# ngptv.net
KiCad netlist of a schematic drawn in EAGLE
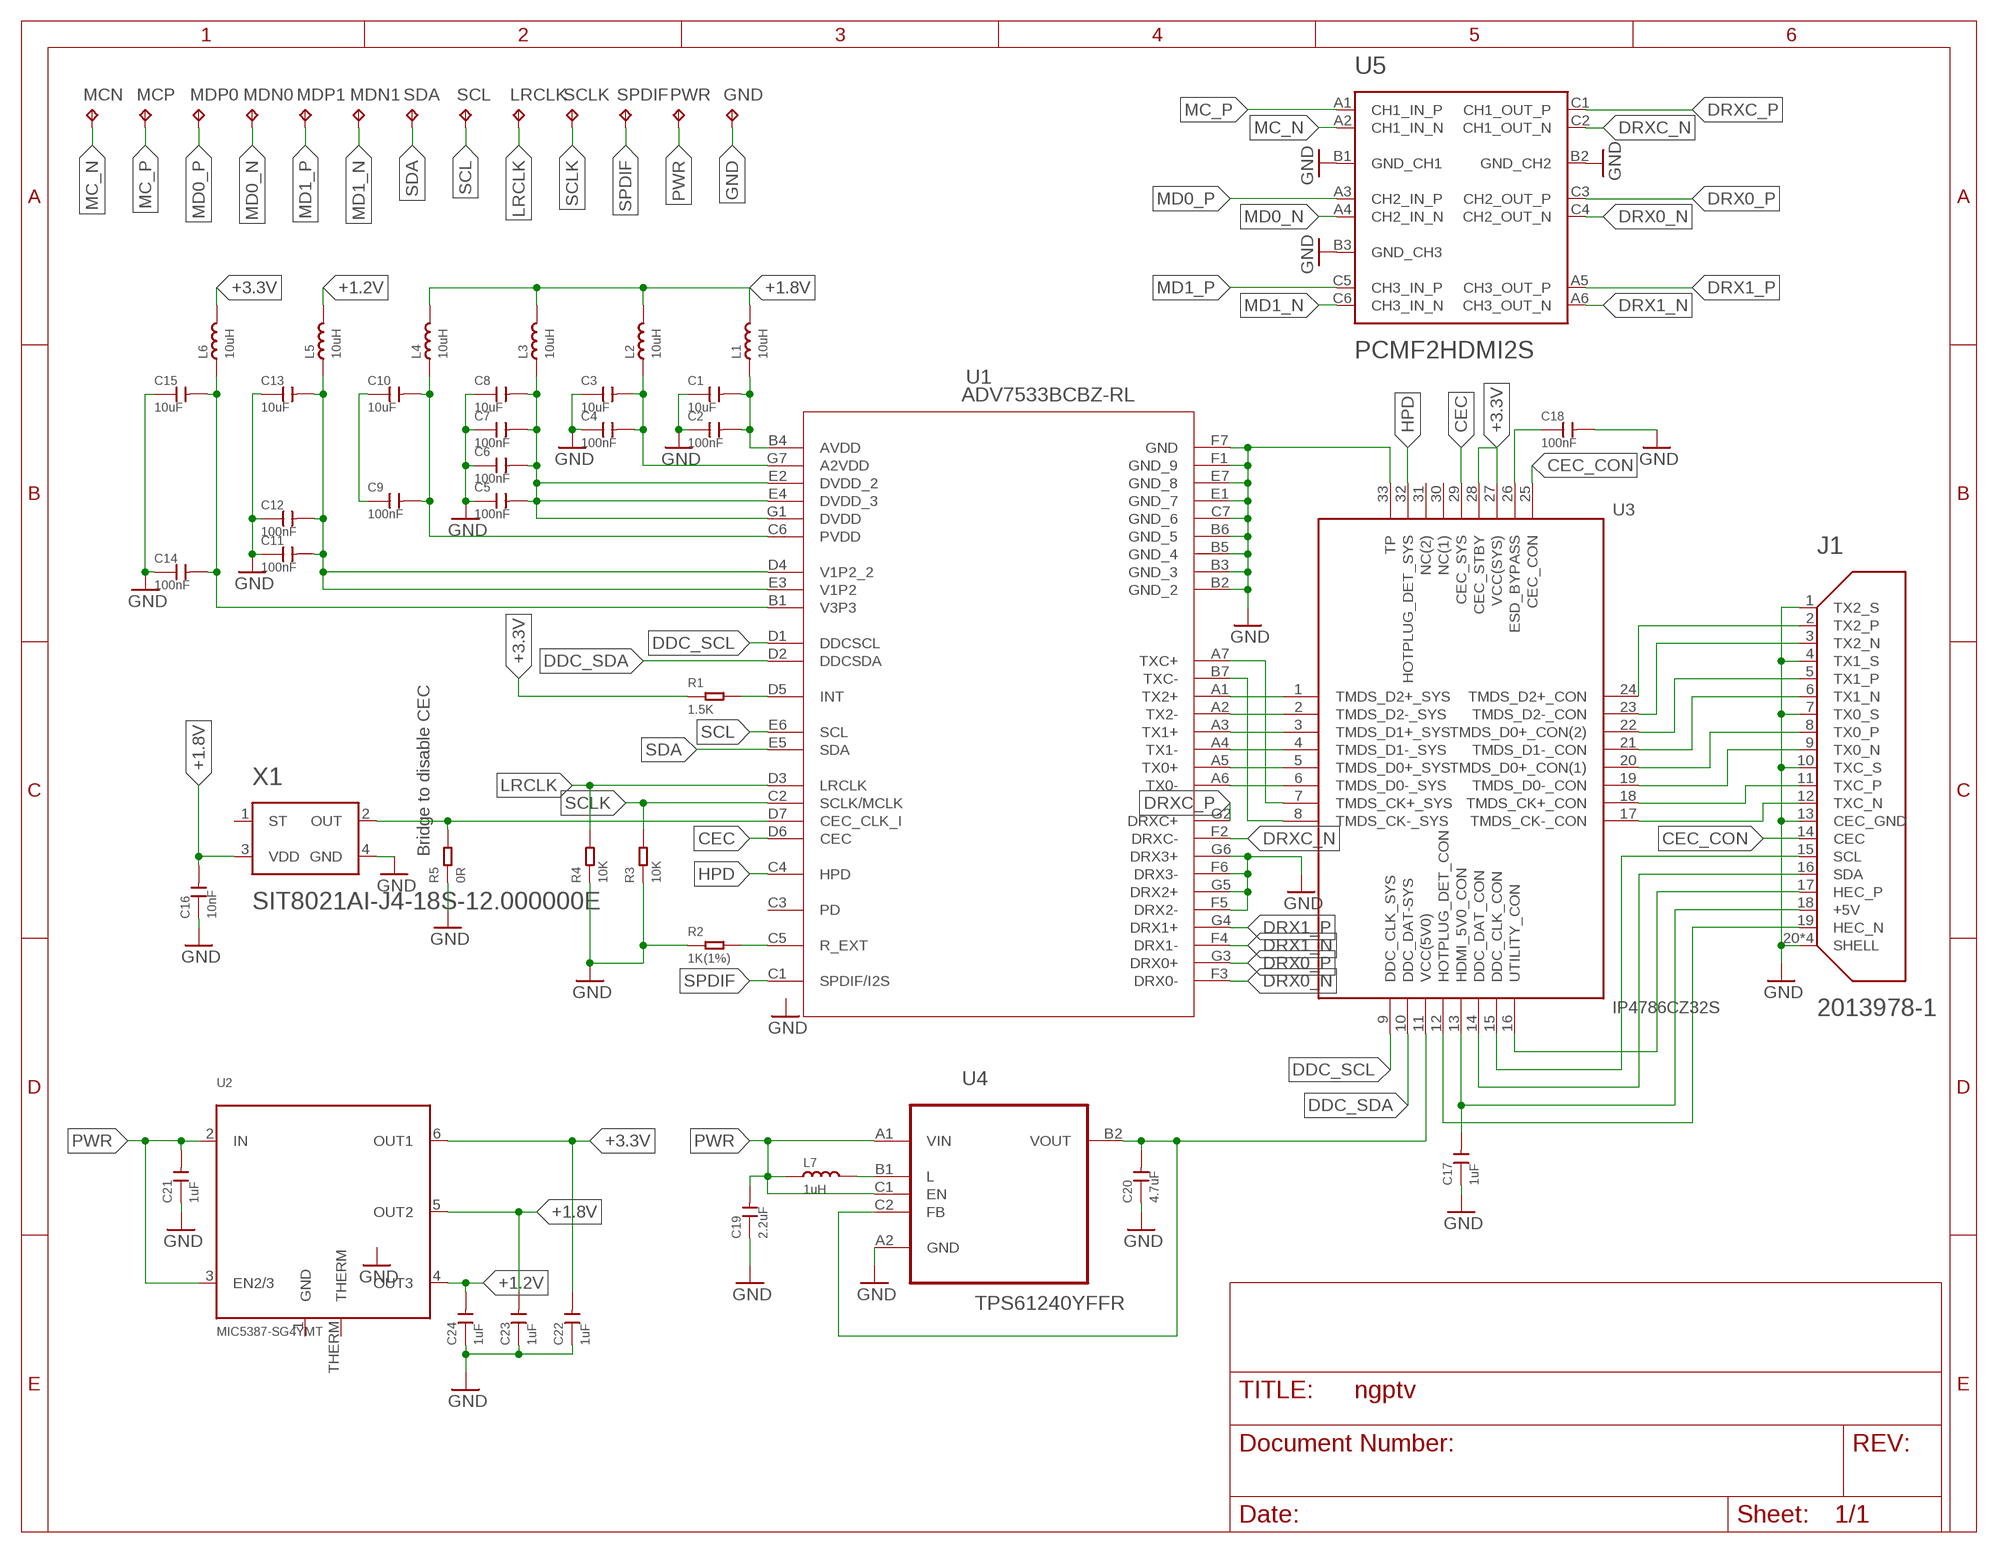
[diagram p0: schematic, sheet 1]

(export (version "E")
  (design (tool "Eeschema 10.0.6"))
  (components
    (comp (ref "C1")
      (value "10uF")
      (footprint "eagle-import:C0402")
      (fields (field (name "MPN") "CC0402MRX5R5BB106"))
      (libsource (lib "eagle-import") (part "CERAMIC-10UF-6.3V-20%-X5R(0402)"))
    )
    (comp (ref "C2")
      (value "100nF")
      (footprint "eagle-import:C0402")
      (fields (field (name "MPN") "CC0402MRX5R5BB106"))
      (libsource (lib "eagle-import") (part "CERAMIC-10UF-6.3V-20%-X5R(0402)"))
    )
    (comp (ref "C3")
      (value "10uF")
      (footprint "eagle-import:C0402")
      (fields (field (name "MPN") "CC0402MRX5R5BB106"))
      (libsource (lib "eagle-import") (part "CERAMIC-10UF-6.3V-20%-X5R(0402)"))
    )
    (comp (ref "C4")
      (value "100nF")
      (footprint "eagle-import:C0402")
      (fields (field (name "MPN") "CC0402MRX5R5BB106"))
      (libsource (lib "eagle-import") (part "CERAMIC-10UF-6.3V-20%-X5R(0402)"))
    )
    (comp (ref "C5")
      (value "100nF")
      (footprint "eagle-import:C0402")
      (fields (field (name "MPN") "CC0402MRX5R5BB106"))
      (libsource (lib "eagle-import") (part "CERAMIC-10UF-6.3V-20%-X5R(0402)"))
    )
    (comp (ref "C6")
      (value "100nF")
      (footprint "eagle-import:C0402")
      (fields (field (name "MPN") "CC0402MRX5R5BB106"))
      (libsource (lib "eagle-import") (part "CERAMIC-10UF-6.3V-20%-X5R(0402)"))
    )
    (comp (ref "C7")
      (value "100nF")
      (footprint "eagle-import:C0402")
      (fields (field (name "MPN") "CC0402MRX5R5BB106"))
      (libsource (lib "eagle-import") (part "CERAMIC-10UF-6.3V-20%-X5R(0402)"))
    )
    (comp (ref "C8")
      (value "10uF")
      (footprint "eagle-import:C0402")
      (fields (field (name "MPN") "CC0402MRX5R5BB106"))
      (libsource (lib "eagle-import") (part "CERAMIC-10UF-6.3V-20%-X5R(0402)"))
    )
    (comp (ref "C9")
      (value "100nF")
      (footprint "eagle-import:C0402")
      (fields (field (name "MPN") "CC0402MRX5R5BB106"))
      (libsource (lib "eagle-import") (part "CERAMIC-10UF-6.3V-20%-X5R(0402)"))
    )
    (comp (ref "C10")
      (value "10uF")
      (footprint "eagle-import:C0402")
      (fields (field (name "MPN") "CC0402MRX5R5BB106"))
      (libsource (lib "eagle-import") (part "CERAMIC-10UF-6.3V-20%-X5R(0402)"))
    )
    (comp (ref "C11")
      (value "100nF")
      (footprint "eagle-import:C0402")
      (fields (field (name "MPN") "CC0402MRX5R5BB106"))
      (libsource (lib "eagle-import") (part "CERAMIC-10UF-6.3V-20%-X5R(0402)"))
    )
    (comp (ref "C12")
      (value "100nF")
      (footprint "eagle-import:C0402")
      (fields (field (name "MPN") "CC0402MRX5R5BB106"))
      (libsource (lib "eagle-import") (part "CERAMIC-10UF-6.3V-20%-X5R(0402)"))
    )
    (comp (ref "C13")
      (value "10uF")
      (footprint "eagle-import:C0402")
      (fields (field (name "MPN") "CC0402MRX5R5BB106"))
      (libsource (lib "eagle-import") (part "CERAMIC-10UF-6.3V-20%-X5R(0402)"))
    )
    (comp (ref "C14")
      (value "100nF")
      (footprint "eagle-import:C0402")
      (fields (field (name "MPN") "CC0402MRX5R5BB106"))
      (libsource (lib "eagle-import") (part "CERAMIC-10UF-6.3V-20%-X5R(0402)"))
    )
    (comp (ref "C15")
      (value "10uF")
      (footprint "eagle-import:C0402")
      (fields (field (name "MPN") "CC0402MRX5R5BB106"))
      (libsource (lib "eagle-import") (part "CERAMIC-10UF-6.3V-20%-X5R(0402)"))
    )
    (comp (ref "C16")
      (value "10nF")
      (footprint "eagle-import:C0402")
      (fields (field (name "MPN") "CC0402MRX5R5BB106"))
      (libsource (lib "eagle-import") (part "CERAMIC-10UF-6.3V-20%-X5R(0402)"))
    )
    (comp (ref "C17")
      (value "1uF")
      (footprint "eagle-import:C0402")
      (fields (field (name "MPN") "CC0402KRX5R5BB105"))
      (libsource (lib "eagle-import") (part "CERAMIC-1UF-6.3V-10%-X5R(0402)"))
    )
    (comp (ref "C18")
      (value "100nF")
      (footprint "eagle-import:C0402")
      (fields (field (name "MPN") "CC0402KRX5R5BB105"))
      (libsource (lib "eagle-import") (part "CERAMIC-1UF-6.3V-10%-X5R(0402)"))
    )
    (comp (ref "C19")
      (value "2.2uF")
      (footprint "eagle-import:C0402")
      (fields (field (name "MPN") "CC0402KRX7R9BB222"))
      (libsource (lib "eagle-import") (part "CERAMIC-2.2NF-50V-10%-X7R(0402)"))
    )
    (comp (ref "C20")
      (value "4.7uF")
      (footprint "eagle-import:C0402")
      (fields (field (name "MPN") "CC0402MRX5R5BB475"))
      (libsource (lib "eagle-import") (part "CERAMIC-4.7UF-6.3V-20%-X5R(0402)"))
    )
    (comp (ref "C21")
      (value "1uF")
      (footprint "eagle-import:C0402")
      (fields (field (name "MPN") "CC0402KRX5R5BB105"))
      (libsource (lib "eagle-import") (part "CERAMIC-1UF-6.3V-10%-X5R(0402)"))
    )
    (comp (ref "C22")
      (value "1uF")
      (footprint "eagle-import:C0402")
      (fields (field (name "MPN") "CC0402KRX5R5BB105"))
      (libsource (lib "eagle-import") (part "CERAMIC-1UF-6.3V-10%-X5R(0402)"))
    )
    (comp (ref "C23")
      (value "1uF")
      (footprint "eagle-import:C0402")
      (fields (field (name "MPN") "CC0402KRX5R5BB105"))
      (libsource (lib "eagle-import") (part "CERAMIC-1UF-6.3V-10%-X5R(0402)"))
    )
    (comp (ref "C24")
      (value "1uF")
      (footprint "eagle-import:C0402")
      (fields (field (name "MPN") "CC0402KRX5R5BB105"))
      (libsource (lib "eagle-import") (part "CERAMIC-1UF-6.3V-10%-X5R(0402)"))
    )
    (comp (ref "GND")
      (value "TPTP12R")
      (footprint "eagle-import:TP12R")
      (libsource (lib "eagle-import") (part "TPTP12R"))
    )
    (comp (ref "J1")
      (value "2013978-1")
      (footprint "eagle-import:DIP-SMT")
      (libsource (lib "eagle-import") (part "2013978-1"))
    )
    (comp (ref "L1")
      (value "10uH")
      (footprint "eagle-import:L0603")
      (fields (field (name "MPN") "BLM18AG121SN1D"))
      (libsource (lib "eagle-import") (part "SMD-FERRITE-CHIP-120-OHM-500MA(0603)"))
    )
    (comp (ref "L2")
      (value "10uH")
      (footprint "eagle-import:L0603")
      (fields (field (name "MPN") "BLM18AG121SN1D"))
      (libsource (lib "eagle-import") (part "SMD-FERRITE-CHIP-120-OHM-500MA(0603)"))
    )
    (comp (ref "L3")
      (value "10uH")
      (footprint "eagle-import:L0603")
      (fields (field (name "MPN") "BLM18AG121SN1D"))
      (libsource (lib "eagle-import") (part "SMD-FERRITE-CHIP-120-OHM-500MA(0603)"))
    )
    (comp (ref "L4")
      (value "10uH")
      (footprint "eagle-import:L0603")
      (fields (field (name "MPN") "BLM18AG121SN1D"))
      (libsource (lib "eagle-import") (part "SMD-FERRITE-CHIP-120-OHM-500MA(0603)"))
    )
    (comp (ref "L5")
      (value "10uH")
      (footprint "eagle-import:L0603")
      (fields (field (name "MPN") "BLM18AG121SN1D"))
      (libsource (lib "eagle-import") (part "SMD-FERRITE-CHIP-120-OHM-500MA(0603)"))
    )
    (comp (ref "L6")
      (value "10uH")
      (footprint "eagle-import:L0603")
      (fields (field (name "MPN") "BLM18AG121SN1D"))
      (libsource (lib "eagle-import") (part "SMD-FERRITE-CHIP-120-OHM-500MA(0603)"))
    )
    (comp (ref "L7")
      (value "1uH")
      (footprint "eagle-import:L0603")
      (fields (field (name "MPN") "BLM18AG121SN1D"))
      (libsource (lib "eagle-import") (part "SMD-FERRITE-CHIP-120-OHM-500MA(0603)"))
    )
    (comp (ref "LRCLK")
      (value "TPTP10R")
      (footprint "eagle-import:TP10R")
      (libsource (lib "eagle-import") (part "TPTP10R"))
    )
    (comp (ref "MCN")
      (value "TPTP10R")
      (footprint "eagle-import:TP10R")
      (libsource (lib "eagle-import") (part "TPTP10R"))
    )
    (comp (ref "MCP")
      (value "TPTP10R")
      (footprint "eagle-import:TP10R")
      (libsource (lib "eagle-import") (part "TPTP10R"))
    )
    (comp (ref "MDN0")
      (value "TPTP10R")
      (footprint "eagle-import:TP10R")
      (libsource (lib "eagle-import") (part "TPTP10R"))
    )
    (comp (ref "MDN1")
      (value "TPTP10R")
      (footprint "eagle-import:TP10R")
      (libsource (lib "eagle-import") (part "TPTP10R"))
    )
    (comp (ref "MDP0")
      (value "TPTP10R")
      (footprint "eagle-import:TP10R")
      (libsource (lib "eagle-import") (part "TPTP10R"))
    )
    (comp (ref "MDP1")
      (value "TPTP10R")
      (footprint "eagle-import:TP10R")
      (libsource (lib "eagle-import") (part "TPTP10R"))
    )
    (comp (ref "PWR")
      (value "TPTP12R")
      (footprint "eagle-import:TP12R")
      (libsource (lib "eagle-import") (part "TPTP12R"))
    )
    (comp (ref "R1")
      (value "1.5K")
      (footprint "eagle-import:R0402")
      (fields (field (name "MPN") "RC0402JR-071K5L"))
      (libsource (lib "eagle-import") (part "SMD-RES-1.5K-5%-1/16W(0402)"))
    )
    (comp (ref "R2")
      (value "1K(1%)")
      (footprint "eagle-import:R0402")
      (fields (field (name "MPN") "RC0402JR-071K5L"))
      (libsource (lib "eagle-import") (part "SMD-RES-1.5K-5%-1/16W(0402)"))
    )
    (comp (ref "R3")
      (value "10K")
      (footprint "eagle-import:R0402")
      (fields (field (name "MPN") "RC0402FR-0710KL"))
      (libsource (lib "eagle-import") (part "SMD-RES-10K-1%-1/16W(0402)"))
    )
    (comp (ref "R4")
      (value "10K")
      (footprint "eagle-import:R0402")
      (fields (field (name "MPN") "RC0402FR-0710KL"))
      (libsource (lib "eagle-import") (part "SMD-RES-10K-1%-1/16W(0402)"))
    )
    (comp (ref "R5")
      (value "0R")
      (footprint "eagle-import:R0402")
      (fields (field (name "MPN") "RC0402JR-070RL"))
      (libsource (lib "eagle-import") (part "SMD-RES-0R-5%-1/16W(0402)"))
    )
    (comp (ref "SCL")
      (value "TPTP10R")
      (footprint "eagle-import:TP10R")
      (libsource (lib "eagle-import") (part "TPTP10R"))
    )
    (comp (ref "SCLK")
      (value "TPTP10R")
      (footprint "eagle-import:TP10R")
      (libsource (lib "eagle-import") (part "TPTP10R"))
    )
    (comp (ref "SDA")
      (value "TPTP10R")
      (footprint "eagle-import:TP10R")
      (libsource (lib "eagle-import") (part "TPTP10R"))
    )
    (comp (ref "SPDIF")
      (value "TPTP10R")
      (footprint "eagle-import:TP10R")
      (libsource (lib "eagle-import") (part "TPTP10R"))
    )
    (comp (ref "U1")
      (value "ADV7533BCBZ-RL")
      (footprint "eagle-import:CB_49_1")
      (libsource (lib "eagle-import") (part "ADV7533BCBZ-RL"))
    )
    (comp (ref "U2")
      (value "MIC5387-SG4YMT")
      (footprint "eagle-import:TMLF-6")
      (libsource (lib "eagle-import") (part "VREG_MIC5387"))
    )
    (comp (ref "U3")
      (value "IP4786CZ32S")
      (footprint "eagle-import:QFN40P400X400X50-33N")
      (libsource (lib "eagle-import") (part "IP4786CZ32S"))
    )
    (comp (ref "U4")
      (value "TPS61240YFFR")
      (footprint "eagle-import:BGA6C40P2X3_125X85X63")
      (libsource (lib "eagle-import") (part "TPS61240YFFR"))
    )
    (comp (ref "U5")
      (value "PCMF2HDMI2S")
      (footprint "eagle-import:WLCSP15")
      (libsource (lib "eagle-import") (part "PCMF2HDMI2S"))
    )
    (comp (ref "X1")
      (value "SIT8021AI-J4-18S-12.000000E")
      (footprint "eagle-import:4-UFBGA")
      (libsource (lib "eagle-import") (part "SIT8021"))
    )
  )
  (nets
    (net (code "1") (name "+1.2V") (class "Default")
      (node (ref "C24") (pin "2") (pinfunction "2_2") (pintype "passive"))
      (node (ref "L5") (pin "2") (pinfunction "2_2") (pintype "passive"))
      (node (ref "U2") (pin "4") (pinfunction "OUT3_4") (pintype "bidirectional"))
    )
    (net (code "2") (name "+1.8V") (class "Default")
      (node (ref "C16") (pin "2") (pinfunction "2_2") (pintype "passive"))
      (node (ref "C23") (pin "2") (pinfunction "2_2") (pintype "passive"))
      (node (ref "L1") (pin "2") (pinfunction "2_2") (pintype "passive"))
      (node (ref "L2") (pin "2") (pinfunction "2_2") (pintype "passive"))
      (node (ref "L3") (pin "2") (pinfunction "2_2") (pintype "passive"))
      (node (ref "L4") (pin "2") (pinfunction "2_2") (pintype "passive"))
      (node (ref "U2") (pin "5") (pinfunction "OUT2_5") (pintype "bidirectional"))
      (node (ref "X1") (pin "3") (pinfunction "VDD_3") (pintype "power_in"))
    )
    (net (code "3") (name "+3.3V") (class "Default")
      (node (ref "C22") (pin "2") (pinfunction "2_2") (pintype "passive"))
      (node (ref "L6") (pin "2") (pinfunction "2_2") (pintype "passive"))
      (node (ref "R1") (pin "1") (pinfunction "1_1") (pintype "passive"))
      (node (ref "U2") (pin "6") (pinfunction "OUT1_6") (pintype "bidirectional"))
      (node (ref "U3") (pin "27") (pinfunction "VCC(SYS)_27") (pintype "power_in"))
      (node (ref "U3") (pin "28") (pinfunction "CEC_STBY_28") (pintype "passive"))
    )
    (net (code "4") (name "CEC") (class "Default")
      (node (ref "U1") (pin "D6") (pinfunction "CEC_D6") (pintype "passive"))
      (node (ref "U3") (pin "29") (pinfunction "CEC_SYS_29") (pintype "passive"))
    )
    (net (code "5") (name "CEC_CON") (class "Default")
      (node (ref "J1") (pin "14") (pinfunction "CEC_14") (pintype "bidirectional"))
      (node (ref "U3") (pin "25") (pinfunction "CEC_CON_25") (pintype "passive"))
    )
    (net (code "6") (name "DDC_SCL") (class "Default")
      (node (ref "U1") (pin "D1") (pinfunction "DDCSCL_D1") (pintype "passive"))
      (node (ref "U3") (pin "9") (pinfunction "DDC_CLK_SYS_9") (pintype "input"))
    )
    (net (code "7") (name "DDC_SDA") (class "Default")
      (node (ref "U1") (pin "D2") (pinfunction "DDCSDA_D2") (pintype "passive"))
      (node (ref "U3") (pin "10") (pinfunction "DDC_DAT-SYS_10") (pintype "passive"))
    )
    (net (code "8") (name "DRX0_N") (class "Default")
      (node (ref "U1") (pin "F3") (pinfunction "DRX0-_F3") (pintype "passive"))
      (node (ref "U5") (pin "C4") (pinfunction "CH2_OUT_N_C4") (pintype "bidirectional"))
    )
    (net (code "9") (name "DRX0_P") (class "Default")
      (node (ref "U1") (pin "G3") (pinfunction "DRX0+_G3") (pintype "passive"))
      (node (ref "U5") (pin "C3") (pinfunction "CH2_OUT_P_C3") (pintype "bidirectional"))
    )
    (net (code "10") (name "DRX1_N") (class "Default")
      (node (ref "U1") (pin "F4") (pinfunction "DRX1-_F4") (pintype "passive"))
      (node (ref "U5") (pin "A6") (pinfunction "CH3_OUT_N_A6") (pintype "bidirectional"))
    )
    (net (code "11") (name "DRX1_P") (class "Default")
      (node (ref "U1") (pin "G4") (pinfunction "DRX1+_G4") (pintype "passive"))
      (node (ref "U5") (pin "A5") (pinfunction "CH3_OUT_P_A5") (pintype "bidirectional"))
    )
    (net (code "12") (name "DRXC_N") (class "Default")
      (node (ref "U1") (pin "F2") (pinfunction "DRXC-_F2") (pintype "passive"))
      (node (ref "U5") (pin "C2") (pinfunction "CH1_OUT_N_C2") (pintype "bidirectional"))
    )
    (net (code "13") (name "DRXC_P") (class "Default")
      (node (ref "U1") (pin "G2") (pinfunction "DRXC+_G2") (pintype "passive"))
      (node (ref "U5") (pin "C1") (pinfunction "CH1_OUT_P_C1") (pintype "bidirectional"))
    )
    (net (code "14") (name "GND") (class "Default")
      (node (ref "C1") (pin "1") (pinfunction "1_1") (pintype "passive"))
      (node (ref "C11") (pin "1") (pinfunction "1_1") (pintype "passive"))
      (node (ref "C12") (pin "1") (pinfunction "1_1") (pintype "passive"))
      (node (ref "C13") (pin "1") (pinfunction "1_1") (pintype "passive"))
      (node (ref "C14") (pin "1") (pinfunction "1_1") (pintype "passive"))
      (node (ref "C15") (pin "1") (pinfunction "1_1") (pintype "passive"))
      (node (ref "C16") (pin "1") (pinfunction "1_1") (pintype "passive"))
      (node (ref "C17") (pin "1") (pinfunction "1_1") (pintype "passive"))
      (node (ref "C18") (pin "2") (pinfunction "2_2") (pintype "passive"))
      (node (ref "C19") (pin "1") (pinfunction "1_1") (pintype "passive"))
      (node (ref "C2") (pin "1") (pinfunction "1_1") (pintype "passive"))
      (node (ref "C20") (pin "1") (pinfunction "1_1") (pintype "passive"))
      (node (ref "C21") (pin "1") (pinfunction "1_1") (pintype "passive"))
      (node (ref "C22") (pin "1") (pinfunction "1_1") (pintype "passive"))
      (node (ref "C23") (pin "1") (pinfunction "1_1") (pintype "passive"))
      (node (ref "C24") (pin "1") (pinfunction "1_1") (pintype "passive"))
      (node (ref "C3") (pin "1") (pinfunction "1_1") (pintype "passive"))
      (node (ref "C4") (pin "1") (pinfunction "1_1") (pintype "passive"))
      (node (ref "C5") (pin "1") (pinfunction "1_1") (pintype "passive"))
      (node (ref "C6") (pin "1") (pinfunction "1_1") (pintype "passive"))
      (node (ref "C7") (pin "1") (pinfunction "1_1") (pintype "passive"))
      (node (ref "C8") (pin "1") (pinfunction "1_1") (pintype "passive"))
      (node (ref "GND") (pin "TP") (pinfunction "TP_TP") (pintype "input"))
      (node (ref "J1") (pin "1") (pinfunction "TX2_S_1") (pintype "bidirectional"))
      (node (ref "J1") (pin "10") (pinfunction "TXC_S_10") (pintype "bidirectional"))
      (node (ref "J1") (pin "13") (pinfunction "CEC_GND_13") (pintype "bidirectional"))
      (node (ref "J1") (pin "20") (pinfunction "SHELL_20") (pintype "bidirectional"))
      (node (ref "J1") (pin "21") (pinfunction "SHELL_21") (pintype "bidirectional"))
      (node (ref "J1") (pin "22") (pinfunction "SHELL_22") (pintype "bidirectional"))
      (node (ref "J1") (pin "23") (pinfunction "SHELL_23") (pintype "bidirectional"))
      (node (ref "J1") (pin "4") (pinfunction "TX1_S_4") (pintype "bidirectional"))
      (node (ref "J1") (pin "7") (pinfunction "TX0_S_7") (pintype "bidirectional"))
      (node (ref "R2") (pin "1") (pinfunction "1_1") (pintype "passive"))
      (node (ref "R3") (pin "1") (pinfunction "1_1") (pintype "passive"))
      (node (ref "R4") (pin "1") (pinfunction "1_1") (pintype "passive"))
      (node (ref "R5") (pin "1") (pinfunction "1_1") (pintype "passive"))
      (node (ref "U1") (pin "B2") (pinfunction "GND_2_B2") (pintype "passive"))
      (node (ref "U1") (pin "B3") (pinfunction "GND_3_B3") (pintype "passive"))
      (node (ref "U1") (pin "B5") (pinfunction "GND_4_B5") (pintype "passive"))
      (node (ref "U1") (pin "B6") (pinfunction "GND_5_B6") (pintype "passive"))
      (node (ref "U1") (pin "C7") (pinfunction "GND_6_C7") (pintype "passive"))
      (node (ref "U1") (pin "E1") (pinfunction "GND_7_E1") (pintype "passive"))
      (node (ref "U1") (pin "E7") (pinfunction "GND_8_E7") (pintype "passive"))
      (node (ref "U1") (pin "F1") (pinfunction "GND_9_F1") (pintype "passive"))
      (node (ref "U1") (pin "F5") (pinfunction "DRX2-_F5") (pintype "passive"))
      (node (ref "U1") (pin "F6") (pinfunction "DRX3-_F6") (pintype "passive"))
      (node (ref "U1") (pin "F7") (pinfunction "GND_F7") (pintype "passive"))
      (node (ref "U1") (pin "G5") (pinfunction "DRX2+_G5") (pintype "passive"))
      (node (ref "U1") (pin "G6") (pinfunction "DRX3+_G6") (pintype "passive"))
      (node (ref "U3") (pin "33") (pinfunction "TP_33") (pintype "passive"))
      (node (ref "U4") (pin "A2") (pinfunction "GND_A2") (pintype "passive"))
      (node (ref "U5") (pin "B1") (pinfunction "GND_CH1_B1") (pintype "power_in"))
      (node (ref "U5") (pin "B2") (pinfunction "GND_CH2_B2") (pintype "power_in"))
      (node (ref "U5") (pin "B3") (pinfunction "GND_CH3_B3") (pintype "power_in"))
      (node (ref "X1") (pin "4") (pinfunction "GND_4") (pintype "power_in"))
    )
    (net (code "15") (name "HPD") (class "Default")
      (node (ref "U1") (pin "C4") (pinfunction "HPD_C4") (pintype "passive"))
      (node (ref "U3") (pin "32") (pinfunction "HOTPLUG_DET_SYS_32") (pintype "passive"))
    )
    (net (code "16") (name "LRCLK") (class "Default")
      (node (ref "LRCLK") (pin "TP") (pinfunction "TP_TP") (pintype "input"))
      (node (ref "R4") (pin "2") (pinfunction "2_2") (pintype "passive"))
      (node (ref "U1") (pin "D3") (pinfunction "LRCLK_D3") (pintype "passive"))
    )
    (net (code "17") (name "MC_N") (class "Default")
      (node (ref "MCN") (pin "TP") (pinfunction "TP_TP") (pintype "input"))
      (node (ref "U5") (pin "A2") (pinfunction "CH1_IN_N_A2") (pintype "bidirectional"))
    )
    (net (code "18") (name "MC_P") (class "Default")
      (node (ref "MCP") (pin "TP") (pinfunction "TP_TP") (pintype "input"))
      (node (ref "U5") (pin "A1") (pinfunction "CH1_IN_P_A1") (pintype "bidirectional"))
    )
    (net (code "19") (name "MD0_N") (class "Default")
      (node (ref "MDN0") (pin "TP") (pinfunction "TP_TP") (pintype "input"))
      (node (ref "U5") (pin "A4") (pinfunction "CH2_IN_N_A4") (pintype "bidirectional"))
    )
    (net (code "20") (name "MD0_P") (class "Default")
      (node (ref "MDP0") (pin "TP") (pinfunction "TP_TP") (pintype "input"))
      (node (ref "U5") (pin "A3") (pinfunction "CH2_IN_P_A3") (pintype "bidirectional"))
    )
    (net (code "21") (name "MD1_N") (class "Default")
      (node (ref "MDN1") (pin "TP") (pinfunction "TP_TP") (pintype "input"))
      (node (ref "U5") (pin "C6") (pinfunction "CH3_IN_N_C6") (pintype "bidirectional"))
    )
    (net (code "22") (name "MD1_P") (class "Default")
      (node (ref "MDP1") (pin "TP") (pinfunction "TP_TP") (pintype "input"))
      (node (ref "U5") (pin "C5") (pinfunction "CH3_IN_P_C5") (pintype "bidirectional"))
    )
    (net (code "23") (name "Net-(C10-Pad1)") (class "Default")
      (node (ref "C10") (pin "1") (pinfunction "1_1") (pintype "passive"))
      (node (ref "C9") (pin "1") (pinfunction "1_1") (pintype "passive"))
    )
    (net (code "24") (name "Net-(J1-+5V)") (class "Default")
      (node (ref "C17") (pin "2") (pinfunction "2_2") (pintype "passive"))
      (node (ref "J1") (pin "18") (pinfunction "+5V_18") (pintype "power_in"))
      (node (ref "U3") (pin "13") (pinfunction "HDMI_5V0_CON_13") (pintype "passive"))
    )
    (net (code "25") (name "Net-(J1-HEC_N)") (class "Default")
      (node (ref "J1") (pin "19") (pinfunction "HEC_N_19") (pintype "bidirectional"))
      (node (ref "U3") (pin "12") (pinfunction "HOTPLUG_DET_CON_12") (pintype "passive"))
    )
    (net (code "26") (name "Net-(J1-HEC_P)") (class "Default")
      (node (ref "J1") (pin "17") (pinfunction "HEC_P_17") (pintype "bidirectional"))
      (node (ref "U3") (pin "16") (pinfunction "UTILITY_CON_16") (pintype "passive"))
    )
    (net (code "27") (name "Net-(J1-SCL)") (class "Default")
      (node (ref "J1") (pin "15") (pinfunction "SCL_15") (pintype "bidirectional"))
      (node (ref "U3") (pin "15") (pinfunction "DDC_CLK_CON_15") (pintype "input"))
    )
    (net (code "28") (name "Net-(J1-SDA)") (class "Default")
      (node (ref "J1") (pin "16") (pinfunction "SDA_16") (pintype "bidirectional"))
      (node (ref "U3") (pin "14") (pinfunction "DDC_DAT_CON_14") (pintype "passive"))
    )
    (net (code "29") (name "Net-(J1-TX0_N)") (class "Default")
      (node (ref "J1") (pin "9") (pinfunction "TX0_N_9") (pintype "bidirectional"))
      (node (ref "U3") (pin "19") (pinfunction "TMDS_D0-_CON_19") (pintype "passive"))
    )
    (net (code "30") (name "Net-(J1-TX0_P)") (class "Default")
      (node (ref "J1") (pin "8") (pinfunction "TX0_P_8") (pintype "bidirectional"))
      (node (ref "U3") (pin "20") (pinfunction "TMDS_D0+_CON(1)_20") (pintype "passive"))
    )
    (net (code "31") (name "Net-(J1-TX1_N)") (class "Default")
      (node (ref "J1") (pin "6") (pinfunction "TX1_N_6") (pintype "bidirectional"))
      (node (ref "U3") (pin "21") (pinfunction "TMDS_D1-_CON_21") (pintype "passive"))
    )
    (net (code "32") (name "Net-(J1-TX1_P)") (class "Default")
      (node (ref "J1") (pin "5") (pinfunction "TX1_P_5") (pintype "bidirectional"))
      (node (ref "U3") (pin "22") (pinfunction "TMDS_D0+_CON(2)_22") (pintype "passive"))
    )
    (net (code "33") (name "Net-(J1-TX2_N)") (class "Default")
      (node (ref "J1") (pin "3") (pinfunction "TX2_N_3") (pintype "bidirectional"))
      (node (ref "U3") (pin "23") (pinfunction "TMDS_D2-_CON_23") (pintype "passive"))
    )
    (net (code "34") (name "Net-(J1-TX2_P)") (class "Default")
      (node (ref "J1") (pin "2") (pinfunction "TX2_P_2") (pintype "bidirectional"))
      (node (ref "U3") (pin "24") (pinfunction "TMDS_D2+_CON_24") (pintype "passive"))
    )
    (net (code "35") (name "Net-(J1-TXC_N)") (class "Default")
      (node (ref "J1") (pin "12") (pinfunction "TXC_N_12") (pintype "bidirectional"))
      (node (ref "U3") (pin "17") (pinfunction "TMDS_CK-_CON_17") (pintype "passive"))
    )
    (net (code "36") (name "Net-(J1-TXC_P)") (class "Default")
      (node (ref "J1") (pin "11") (pinfunction "TXC_P_11") (pintype "bidirectional"))
      (node (ref "U3") (pin "18") (pinfunction "TMDS_CK+_CON_18") (pintype "passive"))
    )
    (net (code "37") (name "Net-(U1-A2VDD)") (class "Default")
      (node (ref "C3") (pin "2") (pinfunction "2_2") (pintype "passive"))
      (node (ref "C4") (pin "2") (pinfunction "2_2") (pintype "passive"))
      (node (ref "L2") (pin "1") (pinfunction "1_1") (pintype "passive"))
      (node (ref "U1") (pin "G7") (pinfunction "A2VDD_G7") (pintype "passive"))
    )
    (net (code "38") (name "Net-(U1-AVDD)") (class "Default")
      (node (ref "C1") (pin "2") (pinfunction "2_2") (pintype "passive"))
      (node (ref "C2") (pin "2") (pinfunction "2_2") (pintype "passive"))
      (node (ref "L1") (pin "1") (pinfunction "1_1") (pintype "passive"))
      (node (ref "U1") (pin "B4") (pinfunction "AVDD_B4") (pintype "passive"))
    )
    (net (code "39") (name "Net-(U1-CEC_CLK_I)") (class "Default")
      (node (ref "R5") (pin "2") (pinfunction "2_2") (pintype "passive"))
      (node (ref "U1") (pin "D7") (pinfunction "CEC_CLK_I_D7") (pintype "passive"))
      (node (ref "X1") (pin "2") (pinfunction "OUT_2") (pintype "bidirectional"))
    )
    (net (code "40") (name "Net-(U1-DVDD)") (class "Default")
      (node (ref "C5") (pin "2") (pinfunction "2_2") (pintype "passive"))
      (node (ref "C6") (pin "2") (pinfunction "2_2") (pintype "passive"))
      (node (ref "C7") (pin "2") (pinfunction "2_2") (pintype "passive"))
      (node (ref "C8") (pin "2") (pinfunction "2_2") (pintype "passive"))
      (node (ref "L3") (pin "1") (pinfunction "1_1") (pintype "passive"))
      (node (ref "U1") (pin "E2") (pinfunction "DVDD_2_E2") (pintype "passive"))
      (node (ref "U1") (pin "E4") (pinfunction "DVDD_3_E4") (pintype "passive"))
      (node (ref "U1") (pin "G1") (pinfunction "DVDD_G1") (pintype "passive"))
    )
    (net (code "41") (name "Net-(U1-INT)") (class "Default")
      (node (ref "R1") (pin "2") (pinfunction "2_2") (pintype "passive"))
      (node (ref "U1") (pin "D5") (pinfunction "INT_D5") (pintype "passive"))
    )
    (net (code "42") (name "Net-(U1-PVDD)") (class "Default")
      (node (ref "C10") (pin "2") (pinfunction "2_2") (pintype "passive"))
      (node (ref "C9") (pin "2") (pinfunction "2_2") (pintype "passive"))
      (node (ref "L4") (pin "1") (pinfunction "1_1") (pintype "passive"))
      (node (ref "U1") (pin "C6") (pinfunction "PVDD_C6") (pintype "passive"))
    )
    (net (code "43") (name "Net-(U1-R_EXT)") (class "Default")
      (node (ref "R2") (pin "2") (pinfunction "2_2") (pintype "passive"))
      (node (ref "U1") (pin "C5") (pinfunction "R_EXT_C5") (pintype "passive"))
    )
    (net (code "44") (name "Net-(U1-TX0+)") (class "Default")
      (node (ref "U1") (pin "A5") (pinfunction "TX0+_A5") (pintype "passive"))
      (node (ref "U3") (pin "5") (pinfunction "TMDS_D0+_SYS_5") (pintype "passive"))
    )
    (net (code "45") (name "Net-(U1-TX0-)") (class "Default")
      (node (ref "U1") (pin "A6") (pinfunction "TX0-_A6") (pintype "passive"))
      (node (ref "U3") (pin "6") (pinfunction "TMDS_D0-_SYS_6") (pintype "passive"))
    )
    (net (code "46") (name "Net-(U1-TX1+)") (class "Default")
      (node (ref "U1") (pin "A3") (pinfunction "TX1+_A3") (pintype "passive"))
      (node (ref "U3") (pin "3") (pinfunction "TMDS_D1+_SYS_3") (pintype "passive"))
    )
    (net (code "47") (name "Net-(U1-TX1-)") (class "Default")
      (node (ref "U1") (pin "A4") (pinfunction "TX1-_A4") (pintype "passive"))
      (node (ref "U3") (pin "4") (pinfunction "TMDS_D1-_SYS_4") (pintype "passive"))
    )
    (net (code "48") (name "Net-(U1-TX2+)") (class "Default")
      (node (ref "U1") (pin "A1") (pinfunction "TX2+_A1") (pintype "passive"))
      (node (ref "U3") (pin "1") (pinfunction "TMDS_D2+_SYS_1") (pintype "passive"))
    )
    (net (code "49") (name "Net-(U1-TX2-)") (class "Default")
      (node (ref "U1") (pin "A2") (pinfunction "TX2-_A2") (pintype "passive"))
      (node (ref "U3") (pin "2") (pinfunction "TMDS_D2-_SYS_2") (pintype "passive"))
    )
    (net (code "50") (name "Net-(U1-TXC+)") (class "Default")
      (node (ref "U1") (pin "A7") (pinfunction "TXC+_A7") (pintype "passive"))
      (node (ref "U3") (pin "7") (pinfunction "TMDS_CK+_SYS_7") (pintype "passive"))
    )
    (net (code "51") (name "Net-(U1-TXC-)") (class "Default")
      (node (ref "U1") (pin "B7") (pinfunction "TXC-_B7") (pintype "passive"))
      (node (ref "U3") (pin "8") (pinfunction "TMDS_CK-_SYS_8") (pintype "passive"))
    )
    (net (code "52") (name "Net-(U1-V1P2)") (class "Default")
      (node (ref "C11") (pin "2") (pinfunction "2_2") (pintype "passive"))
      (node (ref "C12") (pin "2") (pinfunction "2_2") (pintype "passive"))
      (node (ref "C13") (pin "2") (pinfunction "2_2") (pintype "passive"))
      (node (ref "L5") (pin "1") (pinfunction "1_1") (pintype "passive"))
      (node (ref "U1") (pin "D4") (pinfunction "V1P2_2_D4") (pintype "passive"))
      (node (ref "U1") (pin "E3") (pinfunction "V1P2_E3") (pintype "passive"))
    )
    (net (code "53") (name "Net-(U1-V3P3)") (class "Default")
      (node (ref "C14") (pin "2") (pinfunction "2_2") (pintype "passive"))
      (node (ref "C15") (pin "2") (pinfunction "2_2") (pintype "passive"))
      (node (ref "L6") (pin "1") (pinfunction "1_1") (pintype "passive"))
      (node (ref "U1") (pin "B1") (pinfunction "V3P3_B1") (pintype "passive"))
    )
    (net (code "54") (name "Net-(U3-ESD_BYPASS)") (class "Default")
      (node (ref "C18") (pin "1") (pinfunction "1_1") (pintype "passive"))
      (node (ref "U3") (pin "26") (pinfunction "ESD_BYPASS_26") (pintype "passive"))
    )
    (net (code "55") (name "Net-(U3-VCC(5V0))") (class "Default")
      (node (ref "C20") (pin "2") (pinfunction "2_2") (pintype "passive"))
      (node (ref "U3") (pin "11") (pinfunction "VCC(5V0)_11") (pintype "power_in"))
      (node (ref "U4") (pin "B2") (pinfunction "VOUT_B2") (pintype "output"))
      (node (ref "U4") (pin "C2") (pinfunction "FB_C2") (pintype "input"))
    )
    (net (code "56") (name "Net-(U4-L)") (class "Default")
      (node (ref "L7") (pin "2") (pinfunction "2_2") (pintype "passive"))
      (node (ref "U4") (pin "B1") (pinfunction "L_B1") (pintype "input"))
    )
    (net (code "57") (name "PWR") (class "Default")
      (node (ref "C19") (pin "2") (pinfunction "2_2") (pintype "passive"))
      (node (ref "C21") (pin "2") (pinfunction "2_2") (pintype "passive"))
      (node (ref "L7") (pin "1") (pinfunction "1_1") (pintype "passive"))
      (node (ref "PWR") (pin "TP") (pinfunction "TP_TP") (pintype "input"))
      (node (ref "U2") (pin "2") (pinfunction "IN_2") (pintype "bidirectional"))
      (node (ref "U2") (pin "3") (pinfunction "EN2/3_3") (pintype "bidirectional"))
      (node (ref "U4") (pin "A1") (pinfunction "VIN_A1") (pintype "power_in"))
      (node (ref "U4") (pin "C1") (pinfunction "EN_C1") (pintype "input"))
    )
    (net (code "58") (name "SCL") (class "Default")
      (node (ref "SCL") (pin "TP") (pinfunction "TP_TP") (pintype "input"))
      (node (ref "U1") (pin "E6") (pinfunction "SCL_E6") (pintype "passive"))
    )
    (net (code "59") (name "SCLK") (class "Default")
      (node (ref "R3") (pin "2") (pinfunction "2_2") (pintype "passive"))
      (node (ref "SCLK") (pin "TP") (pinfunction "TP_TP") (pintype "input"))
      (node (ref "U1") (pin "C2") (pinfunction "SCLK/MCLK_C2") (pintype "passive"))
    )
    (net (code "60") (name "SDA") (class "Default")
      (node (ref "SDA") (pin "TP") (pinfunction "TP_TP") (pintype "input"))
      (node (ref "U1") (pin "E5") (pinfunction "SDA_E5") (pintype "passive"))
    )
    (net (code "61") (name "SPDIF") (class "Default")
      (node (ref "SPDIF") (pin "TP") (pinfunction "TP_TP") (pintype "input"))
      (node (ref "U1") (pin "C1") (pinfunction "SPDIF/I2S_C1") (pintype "passive"))
    )
    (net (code "62") (name "unconnected-(U1-PD-PadC3)") (class "Default")
      (node (ref "U1") (pin "C3") (pinfunction "PD_C3") (pintype "passive"))
    )
    (net (code "63") (name "unconnected-(U2-GND-Pad1)") (class "Default")
      (node (ref "U2") (pin "1") (pinfunction "GND_1") (pintype "bidirectional"))
    )
    (net (code "64") (name "unconnected-(U2-PadTHERM)") (class "Default")
      (node (ref "U2") (pin "THERM") (pinfunction "THERM_THERM") (pintype "bidirectional"))
    )
    (net (code "65") (name "unconnected-(U3-NC(1)-Pad30)") (class "Default")
      (node (ref "U3") (pin "30") (pinfunction "NC(1)_30") (pintype "passive"))
    )
    (net (code "66") (name "unconnected-(U3-NC(2)-Pad31)") (class "Default")
      (node (ref "U3") (pin "31") (pinfunction "NC(2)_31") (pintype "passive"))
    )
    (net (code "67") (name "unconnected-(X1-ST-Pad1)") (class "Default")
      (node (ref "X1") (pin "1") (pinfunction "ST_1") (pintype "bidirectional"))
    )
  )
)
